# breakout_v1_0.net
KiCad netlist of a schematic drawn in EAGLE
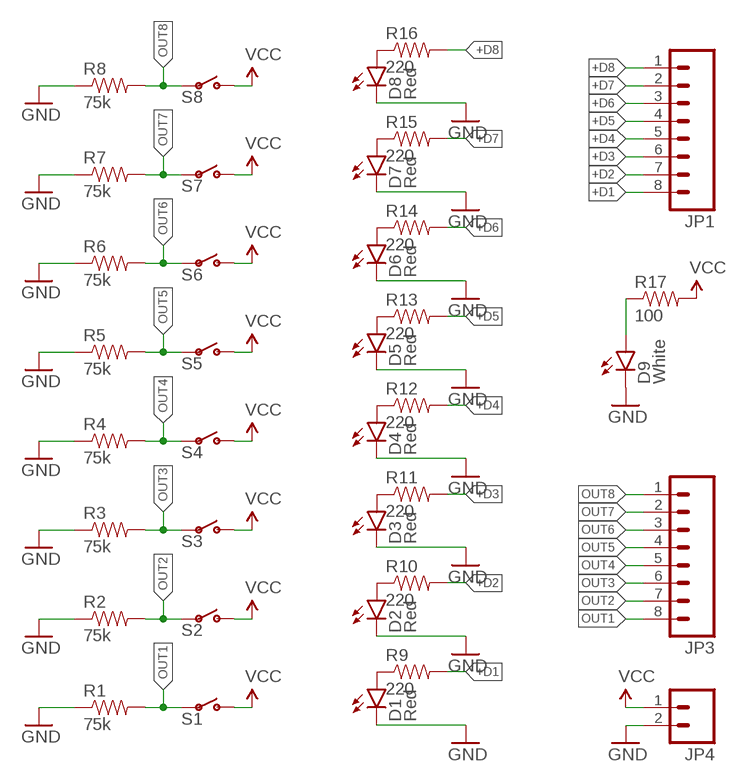
[diagram p0: schematic, sheet 1]

(export (version "E")
  (design (tool "Eeschema 10.0.6"))
  (components
    (comp (ref "D1")
      (value "Red")
      (footprint "eagle-import:0805")
      (libsource (lib "eagle-import") (part "LED0805"))
    )
    (comp (ref "D2")
      (value "Red")
      (footprint "eagle-import:0805")
      (libsource (lib "eagle-import") (part "LED0805"))
    )
    (comp (ref "D3")
      (value "Red")
      (footprint "eagle-import:0805")
      (libsource (lib "eagle-import") (part "LED0805"))
    )
    (comp (ref "D4")
      (value "Red")
      (footprint "eagle-import:0805")
      (libsource (lib "eagle-import") (part "LED0805"))
    )
    (comp (ref "D5")
      (value "Red")
      (footprint "eagle-import:0805")
      (libsource (lib "eagle-import") (part "LED0805"))
    )
    (comp (ref "D6")
      (value "Red")
      (footprint "eagle-import:0805")
      (libsource (lib "eagle-import") (part "LED0805"))
    )
    (comp (ref "D7")
      (value "Red")
      (footprint "eagle-import:0805")
      (libsource (lib "eagle-import") (part "LED0805"))
    )
    (comp (ref "D8")
      (value "Red")
      (footprint "eagle-import:0805")
      (libsource (lib "eagle-import") (part "LED0805"))
    )
    (comp (ref "D9")
      (value "White")
      (footprint "eagle-import:LED-0603")
      (libsource (lib "eagle-import") (part "LED0603"))
    )
    (comp (ref "JP1")
      (value "M08")
      (footprint "eagle-import:1X08_ROUND")
      (libsource (lib "eagle-import") (part "M08"))
    )
    (comp (ref "JP3")
      (value "M08")
      (footprint "eagle-import:1X08_ROUND")
      (libsource (lib "eagle-import") (part "M08"))
    )
    (comp (ref "JP4")
      (value "M02PTH")
      (footprint "eagle-import:1X02")
      (libsource (lib "eagle-import") (part "M02PTH"))
    )
    (comp (ref "R1")
      (value "75k")
      (footprint "eagle-import:0603-RES")
      (libsource (lib "eagle-import") (part "RESISTOR0603"))
    )
    (comp (ref "R2")
      (value "75k")
      (footprint "eagle-import:0603-RES")
      (libsource (lib "eagle-import") (part "RESISTOR0603"))
    )
    (comp (ref "R3")
      (value "75k")
      (footprint "eagle-import:0603-RES")
      (libsource (lib "eagle-import") (part "RESISTOR0603"))
    )
    (comp (ref "R4")
      (value "75k")
      (footprint "eagle-import:0603-RES")
      (libsource (lib "eagle-import") (part "RESISTOR0603"))
    )
    (comp (ref "R5")
      (value "75k")
      (footprint "eagle-import:0603-RES")
      (libsource (lib "eagle-import") (part "RESISTOR0603"))
    )
    (comp (ref "R6")
      (value "75k")
      (footprint "eagle-import:0603-RES")
      (libsource (lib "eagle-import") (part "RESISTOR0603"))
    )
    (comp (ref "R7")
      (value "75k")
      (footprint "eagle-import:0603-RES")
      (libsource (lib "eagle-import") (part "RESISTOR0603"))
    )
    (comp (ref "R8")
      (value "75k")
      (footprint "eagle-import:0603-RES")
      (libsource (lib "eagle-import") (part "RESISTOR0603"))
    )
    (comp (ref "R9")
      (value "220")
      (footprint "eagle-import:0603-RES")
      (libsource (lib "eagle-import") (part "RESISTOR0603"))
    )
    (comp (ref "R10")
      (value "220")
      (footprint "eagle-import:0603-RES")
      (libsource (lib "eagle-import") (part "RESISTOR0603"))
    )
    (comp (ref "R11")
      (value "220")
      (footprint "eagle-import:0603-RES")
      (libsource (lib "eagle-import") (part "RESISTOR0603"))
    )
    (comp (ref "R12")
      (value "220")
      (footprint "eagle-import:0603-RES")
      (libsource (lib "eagle-import") (part "RESISTOR0603"))
    )
    (comp (ref "R13")
      (value "220")
      (footprint "eagle-import:0603-RES")
      (libsource (lib "eagle-import") (part "RESISTOR0603"))
    )
    (comp (ref "R14")
      (value "220")
      (footprint "eagle-import:0603-RES")
      (libsource (lib "eagle-import") (part "RESISTOR0603"))
    )
    (comp (ref "R15")
      (value "220")
      (footprint "eagle-import:0603-RES")
      (libsource (lib "eagle-import") (part "RESISTOR0603"))
    )
    (comp (ref "R16")
      (value "220")
      (footprint "eagle-import:0603-RES")
      (libsource (lib "eagle-import") (part "RESISTOR0603"))
    )
    (comp (ref "R17")
      (value "100")
      (footprint "eagle-import:0603-RES")
      (libsource (lib "eagle-import") (part "RESISTOR0603"))
    )
    (comp (ref "S1")
      (value "SWITCH_SPSTSMD")
      (footprint "eagle-import:5.2X5.2X1.5-SMD")
      (libsource (lib "eagle-import") (part "SWITCH_SPSTSMD"))
    )
    (comp (ref "S2")
      (value "SWITCH_SPSTSMD")
      (footprint "eagle-import:5.2X5.2X1.5-SMD")
      (libsource (lib "eagle-import") (part "SWITCH_SPSTSMD"))
    )
    (comp (ref "S3")
      (value "SWITCH_SPSTSMD")
      (footprint "eagle-import:5.2X5.2X1.5-SMD")
      (libsource (lib "eagle-import") (part "SWITCH_SPSTSMD"))
    )
    (comp (ref "S4")
      (value "SWITCH_SPSTSMD")
      (footprint "eagle-import:5.2X5.2X1.5-SMD")
      (libsource (lib "eagle-import") (part "SWITCH_SPSTSMD"))
    )
    (comp (ref "S5")
      (value "SWITCH_SPSTSMD")
      (footprint "eagle-import:5.2X5.2X1.5-SMD")
      (libsource (lib "eagle-import") (part "SWITCH_SPSTSMD"))
    )
    (comp (ref "S6")
      (value "SWITCH_SPSTSMD")
      (footprint "eagle-import:5.2X5.2X1.5-SMD")
      (libsource (lib "eagle-import") (part "SWITCH_SPSTSMD"))
    )
    (comp (ref "S7")
      (value "SWITCH_SPSTSMD")
      (footprint "eagle-import:5.2X5.2X1.5-SMD")
      (libsource (lib "eagle-import") (part "SWITCH_SPSTSMD"))
    )
    (comp (ref "S8")
      (value "SWITCH_SPSTSMD")
      (footprint "eagle-import:5.2X5.2X1.5-SMD")
      (libsource (lib "eagle-import") (part "SWITCH_SPSTSMD"))
    )
  )
  (nets
    (net (code "1") (name "+D1") (class "Default")
      (node (ref "JP1") (pin "8") (pinfunction "8_8") (pintype "passive"))
      (node (ref "R9") (pin "2") (pinfunction "2_2") (pintype "passive"))
    )
    (net (code "2") (name "+D2") (class "Default")
      (node (ref "JP1") (pin "7") (pinfunction "7_7") (pintype "passive"))
      (node (ref "R10") (pin "2") (pinfunction "2_2") (pintype "passive"))
    )
    (net (code "3") (name "+D3") (class "Default")
      (node (ref "JP1") (pin "6") (pinfunction "6_6") (pintype "passive"))
      (node (ref "R11") (pin "2") (pinfunction "2_2") (pintype "passive"))
    )
    (net (code "4") (name "+D4") (class "Default")
      (node (ref "JP1") (pin "5") (pinfunction "5_5") (pintype "passive"))
      (node (ref "R12") (pin "2") (pinfunction "2_2") (pintype "passive"))
    )
    (net (code "5") (name "+D5") (class "Default")
      (node (ref "JP1") (pin "4") (pinfunction "4_4") (pintype "passive"))
      (node (ref "R13") (pin "2") (pinfunction "2_2") (pintype "passive"))
    )
    (net (code "6") (name "+D6") (class "Default")
      (node (ref "JP1") (pin "3") (pinfunction "3_3") (pintype "passive"))
      (node (ref "R14") (pin "2") (pinfunction "2_2") (pintype "passive"))
    )
    (net (code "7") (name "+D7") (class "Default")
      (node (ref "JP1") (pin "2") (pinfunction "2_2") (pintype "passive"))
      (node (ref "R15") (pin "2") (pinfunction "2_2") (pintype "passive"))
    )
    (net (code "8") (name "+D8") (class "Default")
      (node (ref "JP1") (pin "1") (pinfunction "1_1") (pintype "passive"))
      (node (ref "R16") (pin "2") (pinfunction "2_2") (pintype "passive"))
    )
    (net (code "9") (name "GND") (class "Default")
      (node (ref "D1") (pin "2") (pinfunction "C_2") (pintype "passive"))
      (node (ref "D2") (pin "2") (pinfunction "C_2") (pintype "passive"))
      (node (ref "D3") (pin "2") (pinfunction "C_2") (pintype "passive"))
      (node (ref "D4") (pin "2") (pinfunction "C_2") (pintype "passive"))
      (node (ref "D5") (pin "2") (pinfunction "C_2") (pintype "passive"))
      (node (ref "D6") (pin "2") (pinfunction "C_2") (pintype "passive"))
      (node (ref "D7") (pin "2") (pinfunction "C_2") (pintype "passive"))
      (node (ref "D8") (pin "2") (pinfunction "C_2") (pintype "passive"))
      (node (ref "D9") (pin "C") (pinfunction "C_C") (pintype "passive"))
      (node (ref "JP4") (pin "2") (pinfunction "2_2") (pintype "passive"))
      (node (ref "R1") (pin "1") (pinfunction "1_1") (pintype "passive"))
      (node (ref "R2") (pin "1") (pinfunction "1_1") (pintype "passive"))
      (node (ref "R3") (pin "1") (pinfunction "1_1") (pintype "passive"))
      (node (ref "R4") (pin "1") (pinfunction "1_1") (pintype "passive"))
      (node (ref "R5") (pin "1") (pinfunction "1_1") (pintype "passive"))
      (node (ref "R6") (pin "1") (pinfunction "1_1") (pintype "passive"))
      (node (ref "R7") (pin "1") (pinfunction "1_1") (pintype "passive"))
      (node (ref "R8") (pin "1") (pinfunction "1_1") (pintype "passive"))
    )
    (net (code "10") (name "Net-(D1-A)") (class "Default")
      (node (ref "D1") (pin "1") (pinfunction "A_1") (pintype "passive"))
      (node (ref "R9") (pin "1") (pinfunction "1_1") (pintype "passive"))
    )
    (net (code "11") (name "Net-(D2-A)") (class "Default")
      (node (ref "D2") (pin "1") (pinfunction "A_1") (pintype "passive"))
      (node (ref "R10") (pin "1") (pinfunction "1_1") (pintype "passive"))
    )
    (net (code "12") (name "Net-(D3-A)") (class "Default")
      (node (ref "D3") (pin "1") (pinfunction "A_1") (pintype "passive"))
      (node (ref "R11") (pin "1") (pinfunction "1_1") (pintype "passive"))
    )
    (net (code "13") (name "Net-(D4-A)") (class "Default")
      (node (ref "D4") (pin "1") (pinfunction "A_1") (pintype "passive"))
      (node (ref "R12") (pin "1") (pinfunction "1_1") (pintype "passive"))
    )
    (net (code "14") (name "Net-(D5-A)") (class "Default")
      (node (ref "D5") (pin "1") (pinfunction "A_1") (pintype "passive"))
      (node (ref "R13") (pin "1") (pinfunction "1_1") (pintype "passive"))
    )
    (net (code "15") (name "Net-(D6-A)") (class "Default")
      (node (ref "D6") (pin "1") (pinfunction "A_1") (pintype "passive"))
      (node (ref "R14") (pin "1") (pinfunction "1_1") (pintype "passive"))
    )
    (net (code "16") (name "Net-(D7-A)") (class "Default")
      (node (ref "D7") (pin "1") (pinfunction "A_1") (pintype "passive"))
      (node (ref "R15") (pin "1") (pinfunction "1_1") (pintype "passive"))
    )
    (net (code "17") (name "Net-(D8-A)") (class "Default")
      (node (ref "D8") (pin "1") (pinfunction "A_1") (pintype "passive"))
      (node (ref "R16") (pin "1") (pinfunction "1_1") (pintype "passive"))
    )
    (net (code "18") (name "Net-(D9-PadA)") (class "Default")
      (node (ref "D9") (pin "A") (pinfunction "A_A") (pintype "passive"))
      (node (ref "R17") (pin "1") (pinfunction "1_1") (pintype "passive"))
    )
    (net (code "19") (name "OUT1") (class "Default")
      (node (ref "JP3") (pin "8") (pinfunction "8_8") (pintype "passive"))
      (node (ref "R1") (pin "2") (pinfunction "2_2") (pintype "passive"))
      (node (ref "S1") (pin "P$3") (pinfunction "2_P$3") (pintype "bidirectional"))
    )
    (net (code "20") (name "OUT2") (class "Default")
      (node (ref "JP3") (pin "7") (pinfunction "7_7") (pintype "passive"))
      (node (ref "R2") (pin "2") (pinfunction "2_2") (pintype "passive"))
      (node (ref "S2") (pin "P$3") (pinfunction "2_P$3") (pintype "bidirectional"))
    )
    (net (code "21") (name "OUT3") (class "Default")
      (node (ref "JP3") (pin "6") (pinfunction "6_6") (pintype "passive"))
      (node (ref "R3") (pin "2") (pinfunction "2_2") (pintype "passive"))
      (node (ref "S3") (pin "P$3") (pinfunction "2_P$3") (pintype "bidirectional"))
    )
    (net (code "22") (name "OUT4") (class "Default")
      (node (ref "JP3") (pin "5") (pinfunction "5_5") (pintype "passive"))
      (node (ref "R4") (pin "2") (pinfunction "2_2") (pintype "passive"))
      (node (ref "S4") (pin "P$3") (pinfunction "2_P$3") (pintype "bidirectional"))
    )
    (net (code "23") (name "OUT5") (class "Default")
      (node (ref "JP3") (pin "4") (pinfunction "4_4") (pintype "passive"))
      (node (ref "R5") (pin "2") (pinfunction "2_2") (pintype "passive"))
      (node (ref "S5") (pin "P$3") (pinfunction "2_P$3") (pintype "bidirectional"))
    )
    (net (code "24") (name "OUT6") (class "Default")
      (node (ref "JP3") (pin "3") (pinfunction "3_3") (pintype "passive"))
      (node (ref "R6") (pin "2") (pinfunction "2_2") (pintype "passive"))
      (node (ref "S6") (pin "P$3") (pinfunction "2_P$3") (pintype "bidirectional"))
    )
    (net (code "25") (name "OUT7") (class "Default")
      (node (ref "JP3") (pin "2") (pinfunction "2_2") (pintype "passive"))
      (node (ref "R7") (pin "2") (pinfunction "2_2") (pintype "passive"))
      (node (ref "S7") (pin "P$3") (pinfunction "2_P$3") (pintype "bidirectional"))
    )
    (net (code "26") (name "OUT8") (class "Default")
      (node (ref "JP3") (pin "1") (pinfunction "1_1") (pintype "passive"))
      (node (ref "R8") (pin "2") (pinfunction "2_2") (pintype "passive"))
      (node (ref "S8") (pin "P$3") (pinfunction "2_P$3") (pintype "bidirectional"))
    )
    (net (code "27") (name "VCC") (class "Default")
      (node (ref "JP4") (pin "1") (pinfunction "1_1") (pintype "passive"))
      (node (ref "R17") (pin "2") (pinfunction "2_2") (pintype "passive"))
      (node (ref "S1") (pin "P$1") (pinfunction "1_P$1") (pintype "bidirectional"))
      (node (ref "S2") (pin "P$1") (pinfunction "1_P$1") (pintype "bidirectional"))
      (node (ref "S3") (pin "P$1") (pinfunction "1_P$1") (pintype "bidirectional"))
      (node (ref "S4") (pin "P$1") (pinfunction "1_P$1") (pintype "bidirectional"))
      (node (ref "S5") (pin "P$1") (pinfunction "1_P$1") (pintype "bidirectional"))
      (node (ref "S6") (pin "P$1") (pinfunction "1_P$1") (pintype "bidirectional"))
      (node (ref "S7") (pin "P$1") (pinfunction "1_P$1") (pintype "bidirectional"))
      (node (ref "S8") (pin "P$1") (pinfunction "1_P$1") (pintype "bidirectional"))
    )
  )
)
